# PSU-Unit.net
KiCad netlist of a schematic drawn in EAGLE
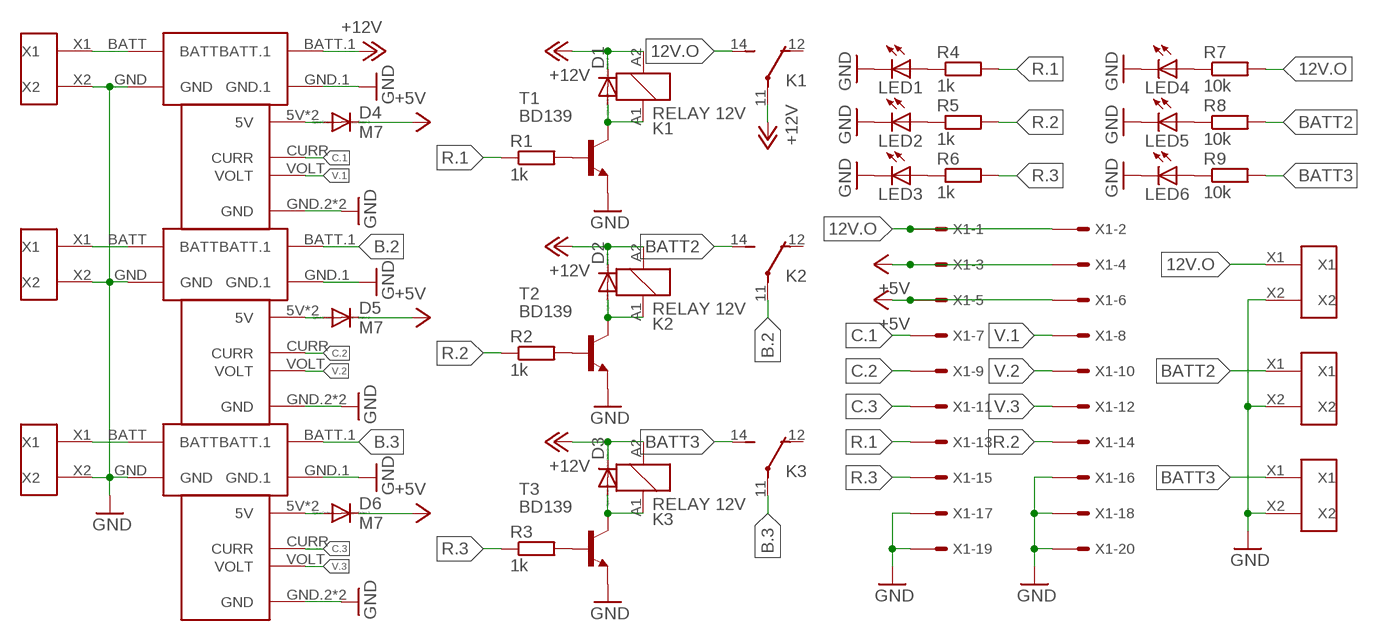
[diagram p0: schematic, sheet 1]

(export (version "E")
  (design (tool "Eeschema 10.0.6"))
  (components
    (comp (ref "D1")
      (value "DIODE-DO214AA")
      (footprint "eagle-import:DO214AA")
      (libsource (lib "eagle-import") (part "DIODE-DO214AA"))
    )
    (comp (ref "D2")
      (value "DIODE-DO214AA")
      (footprint "eagle-import:DO214AA")
      (libsource (lib "eagle-import") (part "DIODE-DO214AA"))
    )
    (comp (ref "D3")
      (value "DIODE-DO214AA")
      (footprint "eagle-import:DO214AA")
      (libsource (lib "eagle-import") (part "DIODE-DO214AA"))
    )
    (comp (ref "D4")
      (value "M7")
      (footprint "eagle-import:DO214AA")
      (libsource (lib "eagle-import") (part "DIODE-DO214AA"))
    )
    (comp (ref "D5")
      (value "M7")
      (footprint "eagle-import:DO214AA")
      (libsource (lib "eagle-import") (part "DIODE-DO214AA"))
    )
    (comp (ref "D6")
      (value "M7")
      (footprint "eagle-import:DO214AA")
      (libsource (lib "eagle-import") (part "DIODE-DO214AA"))
    )
    (comp (ref "K1")
      (value "RELAY 12V")
      (footprint "eagle-import:ZD1")
      (libsource (lib "eagle-import") (part "ZD?132006"))
    )
    (comp (ref "K2")
      (value "RELAY 12V")
      (footprint "eagle-import:ZD1")
      (libsource (lib "eagle-import") (part "ZD?132006"))
    )
    (comp (ref "K3")
      (value "RELAY 12V")
      (footprint "eagle-import:ZD1")
      (libsource (lib "eagle-import") (part "ZD?132006"))
    )
    (comp (ref "LED1")
      (value "LEDCHIPLED_1206")
      (footprint "eagle-import:CHIPLED_1206")
      (libsource (lib "eagle-import") (part "LEDCHIPLED_1206"))
    )
    (comp (ref "LED2")
      (value "LEDCHIPLED_1206")
      (footprint "eagle-import:CHIPLED_1206")
      (libsource (lib "eagle-import") (part "LEDCHIPLED_1206"))
    )
    (comp (ref "LED3")
      (value "LEDCHIPLED_1206")
      (footprint "eagle-import:CHIPLED_1206")
      (libsource (lib "eagle-import") (part "LEDCHIPLED_1206"))
    )
    (comp (ref "LED4")
      (value "LEDCHIPLED_1206")
      (footprint "eagle-import:CHIPLED_1206")
      (libsource (lib "eagle-import") (part "LEDCHIPLED_1206"))
    )
    (comp (ref "LED5")
      (value "LEDCHIPLED_1206")
      (footprint "eagle-import:CHIPLED_1206")
      (libsource (lib "eagle-import") (part "LEDCHIPLED_1206"))
    )
    (comp (ref "LED6")
      (value "LEDCHIPLED_1206")
      (footprint "eagle-import:CHIPLED_1206")
      (libsource (lib "eagle-import") (part "LEDCHIPLED_1206"))
    )
    (comp (ref "R1")
      (value "1k")
      (footprint "eagle-import:R0805")
      (libsource (lib "eagle-import") (part "R-EU_R0805"))
    )
    (comp (ref "R2")
      (value "1k")
      (footprint "eagle-import:R0805")
      (libsource (lib "eagle-import") (part "R-EU_R0805"))
    )
    (comp (ref "R3")
      (value "1k")
      (footprint "eagle-import:R0805")
      (libsource (lib "eagle-import") (part "R-EU_R0805"))
    )
    (comp (ref "R4")
      (value "1k")
      (footprint "eagle-import:R0805")
      (libsource (lib "eagle-import") (part "R-EU_R0805"))
    )
    (comp (ref "R5")
      (value "1k")
      (footprint "eagle-import:R0805")
      (libsource (lib "eagle-import") (part "R-EU_R0805"))
    )
    (comp (ref "R6")
      (value "1k")
      (footprint "eagle-import:R0805")
      (libsource (lib "eagle-import") (part "R-EU_R0805"))
    )
    (comp (ref "R7")
      (value "10k")
      (footprint "eagle-import:R0805")
      (libsource (lib "eagle-import") (part "R-EU_R0805"))
    )
    (comp (ref "R8")
      (value "10k")
      (footprint "eagle-import:R0805")
      (libsource (lib "eagle-import") (part "R-EU_R0805"))
    )
    (comp (ref "R9")
      (value "10k")
      (footprint "eagle-import:R0805")
      (libsource (lib "eagle-import") (part "R-EU_R0805"))
    )
    (comp (ref "T1")
      (value "BD139")
      (footprint "eagle-import:TO126V")
      (libsource (lib "eagle-import") (part "-NPN-TO126V"))
    )
    (comp (ref "T2")
      (value "BD139")
      (footprint "eagle-import:TO126V")
      (libsource (lib "eagle-import") (part "-NPN-TO126V"))
    )
    (comp (ref "T3")
      (value "BD139")
      (footprint "eagle-import:TO126V")
      (libsource (lib "eagle-import") (part "-NPN-TO126V"))
    )
    (comp (ref "U$1")
      (value "APM-POWER-MODULE")
      (footprint "eagle-import:APM-POWER-MODULE")
      (libsource (lib "eagle-import") (part "APM-POWER-MODULE"))
    )
    (comp (ref "U$2")
      (value "APM-MEASURAND")
      (footprint "eagle-import:APM-MEASURAND")
      (libsource (lib "eagle-import") (part "APM-MEASURAND"))
    )
    (comp (ref "U$3")
      (value "APM-POWER-MODULE")
      (footprint "eagle-import:APM-POWER-MODULE")
      (libsource (lib "eagle-import") (part "APM-POWER-MODULE"))
    )
    (comp (ref "U$4")
      (value "APM-MEASURAND")
      (footprint "eagle-import:APM-MEASURAND")
      (libsource (lib "eagle-import") (part "APM-MEASURAND"))
    )
    (comp (ref "U$5")
      (value "APM-POWER-MODULE")
      (footprint "eagle-import:APM-POWER-MODULE")
      (libsource (lib "eagle-import") (part "APM-POWER-MODULE"))
    )
    (comp (ref "U$6")
      (value "APM-MEASURAND")
      (footprint "eagle-import:APM-MEASURAND")
      (libsource (lib "eagle-import") (part "APM-MEASURAND"))
    )
    (comp (ref "U$7")
      (value "T-BLOCK-9.5MM")
      (footprint "eagle-import:T-BLOCK-9.5MM")
      (libsource (lib "eagle-import") (part "T-BLOCK-9.5MM"))
    )
    (comp (ref "U$8")
      (value "T-BLOCK-9.5MM")
      (footprint "eagle-import:T-BLOCK-9.5MM")
      (libsource (lib "eagle-import") (part "T-BLOCK-9.5MM"))
    )
    (comp (ref "U$9")
      (value "T-BLOCK-9.5MM")
      (footprint "eagle-import:T-BLOCK-9.5MM")
      (libsource (lib "eagle-import") (part "T-BLOCK-9.5MM"))
    )
    (comp (ref "U$10")
      (value "T-BLOCK-9.5MM")
      (footprint "eagle-import:T-BLOCK-9.5MM")
      (libsource (lib "eagle-import") (part "T-BLOCK-9.5MM"))
    )
    (comp (ref "U$11")
      (value "T-BLOCK-9.5MM")
      (footprint "eagle-import:T-BLOCK-9.5MM")
      (libsource (lib "eagle-import") (part "T-BLOCK-9.5MM"))
    )
    (comp (ref "U$12")
      (value "T-BLOCK-9.5MM")
      (footprint "eagle-import:T-BLOCK-9.5MM")
      (libsource (lib "eagle-import") (part "T-BLOCK-9.5MM"))
    )
    (comp (ref "X1")
      (value "057-020-1")
      (footprint "eagle-import:057-020-1")
      (libsource (lib "eagle-import") (part "057-020-1"))
    )
  )
  (nets
    (net (code "1") (name "+5V") (class "Default")
      (node (ref "D4") (pin "C") (pinfunction "C_C") (pintype "passive"))
      (node (ref "D5") (pin "C") (pinfunction "C_C") (pintype "passive"))
      (node (ref "D6") (pin "C") (pinfunction "C_C") (pintype "passive"))
      (node (ref "X1") (pin "3") (pinfunction "S_3") (pintype "passive"))
      (node (ref "X1") (pin "4") (pinfunction "S_4") (pintype "passive"))
      (node (ref "X1") (pin "5") (pinfunction "S_5") (pintype "passive"))
      (node (ref "X1") (pin "6") (pinfunction "S_6") (pintype "passive"))
    )
    (net (code "2") (name "+12V") (class "Default")
      (node (ref "D1") (pin "C") (pinfunction "C_C") (pintype "passive"))
      (node (ref "D2") (pin "C") (pinfunction "C_C") (pintype "passive"))
      (node (ref "D3") (pin "C") (pinfunction "C_C") (pintype "passive"))
      (node (ref "K1") (pin "11") (pinfunction "P_11") (pintype "passive"))
      (node (ref "K1") (pin "A2") (pinfunction "2_A2") (pintype "passive"))
      (node (ref "K2") (pin "A2") (pinfunction "2_A2") (pintype "passive"))
      (node (ref "K3") (pin "A2") (pinfunction "2_A2") (pintype "passive"))
      (node (ref "U$1") (pin "BATT.1") (pinfunction "BATT.1_BATT.1") (pintype "bidirectional"))
    )
    (net (code "3") (name "12V.O") (class "Default")
      (node (ref "K1") (pin "14") (pinfunction "S_14") (pintype "passive"))
      (node (ref "R7") (pin "2") (pinfunction "2_2") (pintype "passive"))
      (node (ref "U$10") (pin "X1") (pinfunction "X1_X1") (pintype "bidirectional"))
      (node (ref "X1") (pin "1") (pinfunction "S_1") (pintype "passive"))
      (node (ref "X1") (pin "2") (pinfunction "S_2") (pintype "passive"))
    )
    (net (code "4") (name "B.2") (class "Default")
      (node (ref "K2") (pin "11") (pinfunction "P_11") (pintype "passive"))
      (node (ref "U$3") (pin "BATT.1") (pinfunction "BATT.1_BATT.1") (pintype "bidirectional"))
    )
    (net (code "5") (name "B.3") (class "Default")
      (node (ref "K3") (pin "11") (pinfunction "P_11") (pintype "passive"))
      (node (ref "U$5") (pin "BATT.1") (pinfunction "BATT.1_BATT.1") (pintype "bidirectional"))
    )
    (net (code "6") (name "BATT2") (class "Default")
      (node (ref "K2") (pin "14") (pinfunction "S_14") (pintype "passive"))
      (node (ref "R8") (pin "2") (pinfunction "2_2") (pintype "passive"))
      (node (ref "U$11") (pin "X1") (pinfunction "X1_X1") (pintype "bidirectional"))
    )
    (net (code "7") (name "BATT3") (class "Default")
      (node (ref "K3") (pin "14") (pinfunction "S_14") (pintype "passive"))
      (node (ref "R9") (pin "2") (pinfunction "2_2") (pintype "passive"))
      (node (ref "U$12") (pin "X1") (pinfunction "X1_X1") (pintype "bidirectional"))
    )
    (net (code "8") (name "C.1") (class "Default")
      (node (ref "U$2") (pin "CURR") (pinfunction "CURR_CURR") (pintype "bidirectional"))
      (node (ref "X1") (pin "7") (pinfunction "S_7") (pintype "passive"))
    )
    (net (code "9") (name "C.2") (class "Default")
      (node (ref "U$4") (pin "CURR") (pinfunction "CURR_CURR") (pintype "bidirectional"))
      (node (ref "X1") (pin "9") (pinfunction "S_9") (pintype "passive"))
    )
    (net (code "10") (name "C.3") (class "Default")
      (node (ref "U$6") (pin "CURR") (pinfunction "CURR_CURR") (pintype "bidirectional"))
      (node (ref "X1") (pin "11") (pinfunction "S_11") (pintype "passive"))
    )
    (net (code "11") (name "GND") (class "Default")
      (node (ref "LED1") (pin "C") (pinfunction "C_C") (pintype "passive"))
      (node (ref "LED2") (pin "C") (pinfunction "C_C") (pintype "passive"))
      (node (ref "LED3") (pin "C") (pinfunction "C_C") (pintype "passive"))
      (node (ref "LED4") (pin "C") (pinfunction "C_C") (pintype "passive"))
      (node (ref "LED5") (pin "C") (pinfunction "C_C") (pintype "passive"))
      (node (ref "LED6") (pin "C") (pinfunction "C_C") (pintype "passive"))
      (node (ref "T1") (pin "1") (pinfunction "E_1") (pintype "passive"))
      (node (ref "T2") (pin "1") (pinfunction "E_1") (pintype "passive"))
      (node (ref "T3") (pin "1") (pinfunction "E_1") (pintype "passive"))
      (node (ref "U$1") (pin "GND") (pinfunction "GND_GND") (pintype "bidirectional"))
      (node (ref "U$1") (pin "GND.1") (pinfunction "GND.1_GND.1") (pintype "bidirectional"))
      (node (ref "U$10") (pin "X2") (pinfunction "X2_X2") (pintype "bidirectional"))
      (node (ref "U$11") (pin "X2") (pinfunction "X2_X2") (pintype "bidirectional"))
      (node (ref "U$12") (pin "X2") (pinfunction "X2_X2") (pintype "bidirectional"))
      (node (ref "U$2") (pin "GND.2") (pinfunction "GND_GND.2") (pintype "bidirectional"))
      (node (ref "U$2") (pin "GND.3") (pinfunction "GND_GND.3") (pintype "bidirectional"))
      (node (ref "U$3") (pin "GND") (pinfunction "GND_GND") (pintype "bidirectional"))
      (node (ref "U$3") (pin "GND.1") (pinfunction "GND.1_GND.1") (pintype "bidirectional"))
      (node (ref "U$4") (pin "GND.2") (pinfunction "GND_GND.2") (pintype "bidirectional"))
      (node (ref "U$4") (pin "GND.3") (pinfunction "GND_GND.3") (pintype "bidirectional"))
      (node (ref "U$5") (pin "GND") (pinfunction "GND_GND") (pintype "bidirectional"))
      (node (ref "U$5") (pin "GND.1") (pinfunction "GND.1_GND.1") (pintype "bidirectional"))
      (node (ref "U$6") (pin "GND.2") (pinfunction "GND_GND.2") (pintype "bidirectional"))
      (node (ref "U$6") (pin "GND.3") (pinfunction "GND_GND.3") (pintype "bidirectional"))
      (node (ref "U$7") (pin "X2") (pinfunction "X2_X2") (pintype "bidirectional"))
      (node (ref "U$8") (pin "X2") (pinfunction "X2_X2") (pintype "bidirectional"))
      (node (ref "U$9") (pin "X2") (pinfunction "X2_X2") (pintype "bidirectional"))
      (node (ref "X1") (pin "16") (pinfunction "S_16") (pintype "passive"))
      (node (ref "X1") (pin "17") (pinfunction "S_17") (pintype "passive"))
      (node (ref "X1") (pin "18") (pinfunction "S_18") (pintype "passive"))
      (node (ref "X1") (pin "19") (pinfunction "S_19") (pintype "passive"))
      (node (ref "X1") (pin "20") (pinfunction "S_20") (pintype "passive"))
    )
    (net (code "12") (name "Net-(D4-PadA)") (class "Default")
      (node (ref "D4") (pin "A") (pinfunction "A_A") (pintype "passive"))
      (node (ref "U$2") (pin "5V") (pinfunction "5V_5V") (pintype "bidirectional"))
      (node (ref "U$2") (pin "5V.1") (pinfunction "5V_5V.1") (pintype "bidirectional"))
    )
    (net (code "13") (name "Net-(D5-PadA)") (class "Default")
      (node (ref "D5") (pin "A") (pinfunction "A_A") (pintype "passive"))
      (node (ref "U$4") (pin "5V") (pinfunction "5V_5V") (pintype "bidirectional"))
      (node (ref "U$4") (pin "5V.1") (pinfunction "5V_5V.1") (pintype "bidirectional"))
    )
    (net (code "14") (name "Net-(D6-PadA)") (class "Default")
      (node (ref "D6") (pin "A") (pinfunction "A_A") (pintype "passive"))
      (node (ref "U$6") (pin "5V") (pinfunction "5V_5V") (pintype "bidirectional"))
      (node (ref "U$6") (pin "5V.1") (pinfunction "5V_5V.1") (pintype "bidirectional"))
    )
    (net (code "15") (name "Net-(K1A-1)") (class "Default")
      (node (ref "D1") (pin "A") (pinfunction "A_A") (pintype "passive"))
      (node (ref "K1") (pin "A1") (pinfunction "1_A1") (pintype "passive"))
      (node (ref "T1") (pin "2") (pinfunction "C_2") (pintype "passive"))
    )
    (net (code "16") (name "Net-(K2A-1)") (class "Default")
      (node (ref "D2") (pin "A") (pinfunction "A_A") (pintype "passive"))
      (node (ref "K2") (pin "A1") (pinfunction "1_A1") (pintype "passive"))
      (node (ref "T2") (pin "2") (pinfunction "C_2") (pintype "passive"))
    )
    (net (code "17") (name "Net-(K3A-1)") (class "Default")
      (node (ref "D3") (pin "A") (pinfunction "A_A") (pintype "passive"))
      (node (ref "K3") (pin "A1") (pinfunction "1_A1") (pintype "passive"))
      (node (ref "T3") (pin "2") (pinfunction "C_2") (pintype "passive"))
    )
    (net (code "18") (name "Net-(LED1-PadA)") (class "Default")
      (node (ref "LED1") (pin "A") (pinfunction "A_A") (pintype "passive"))
      (node (ref "R4") (pin "1") (pinfunction "1_1") (pintype "passive"))
    )
    (net (code "19") (name "Net-(LED2-PadA)") (class "Default")
      (node (ref "LED2") (pin "A") (pinfunction "A_A") (pintype "passive"))
      (node (ref "R5") (pin "1") (pinfunction "1_1") (pintype "passive"))
    )
    (net (code "20") (name "Net-(LED3-PadA)") (class "Default")
      (node (ref "LED3") (pin "A") (pinfunction "A_A") (pintype "passive"))
      (node (ref "R6") (pin "1") (pinfunction "1_1") (pintype "passive"))
    )
    (net (code "21") (name "Net-(LED4-PadA)") (class "Default")
      (node (ref "LED4") (pin "A") (pinfunction "A_A") (pintype "passive"))
      (node (ref "R7") (pin "1") (pinfunction "1_1") (pintype "passive"))
    )
    (net (code "22") (name "Net-(LED5-PadA)") (class "Default")
      (node (ref "LED5") (pin "A") (pinfunction "A_A") (pintype "passive"))
      (node (ref "R8") (pin "1") (pinfunction "1_1") (pintype "passive"))
    )
    (net (code "23") (name "Net-(LED6-PadA)") (class "Default")
      (node (ref "LED6") (pin "A") (pinfunction "A_A") (pintype "passive"))
      (node (ref "R9") (pin "1") (pinfunction "1_1") (pintype "passive"))
    )
    (net (code "24") (name "Net-(T1-B)") (class "Default")
      (node (ref "R1") (pin "2") (pinfunction "2_2") (pintype "passive"))
      (node (ref "T1") (pin "3") (pinfunction "B_3") (pintype "passive"))
    )
    (net (code "25") (name "Net-(T2-B)") (class "Default")
      (node (ref "R2") (pin "2") (pinfunction "2_2") (pintype "passive"))
      (node (ref "T2") (pin "3") (pinfunction "B_3") (pintype "passive"))
    )
    (net (code "26") (name "Net-(T3-B)") (class "Default")
      (node (ref "R3") (pin "2") (pinfunction "2_2") (pintype "passive"))
      (node (ref "T3") (pin "3") (pinfunction "B_3") (pintype "passive"))
    )
    (net (code "27") (name "Net-(U$1-PadBATT)") (class "Default")
      (node (ref "U$1") (pin "BATT") (pinfunction "BATT_BATT") (pintype "bidirectional"))
      (node (ref "U$7") (pin "X1") (pinfunction "X1_X1") (pintype "bidirectional"))
    )
    (net (code "28") (name "Net-(U$3-PadBATT)") (class "Default")
      (node (ref "U$3") (pin "BATT") (pinfunction "BATT_BATT") (pintype "bidirectional"))
      (node (ref "U$8") (pin "X1") (pinfunction "X1_X1") (pintype "bidirectional"))
    )
    (net (code "29") (name "Net-(U$5-PadBATT)") (class "Default")
      (node (ref "U$5") (pin "BATT") (pinfunction "BATT_BATT") (pintype "bidirectional"))
      (node (ref "U$9") (pin "X1") (pinfunction "X1_X1") (pintype "bidirectional"))
    )
    (net (code "30") (name "R.1") (class "Default")
      (node (ref "R1") (pin "1") (pinfunction "1_1") (pintype "passive"))
      (node (ref "R4") (pin "2") (pinfunction "2_2") (pintype "passive"))
      (node (ref "X1") (pin "13") (pinfunction "S_13") (pintype "passive"))
    )
    (net (code "31") (name "R.2") (class "Default")
      (node (ref "R2") (pin "1") (pinfunction "1_1") (pintype "passive"))
      (node (ref "R5") (pin "2") (pinfunction "2_2") (pintype "passive"))
      (node (ref "X1") (pin "14") (pinfunction "S_14") (pintype "passive"))
    )
    (net (code "32") (name "R.3") (class "Default")
      (node (ref "R3") (pin "1") (pinfunction "1_1") (pintype "passive"))
      (node (ref "R6") (pin "2") (pinfunction "2_2") (pintype "passive"))
      (node (ref "X1") (pin "15") (pinfunction "S_15") (pintype "passive"))
    )
    (net (code "33") (name "V.1") (class "Default")
      (node (ref "U$2") (pin "VOLT") (pinfunction "VOLT_VOLT") (pintype "bidirectional"))
      (node (ref "X1") (pin "8") (pinfunction "S_8") (pintype "passive"))
    )
    (net (code "34") (name "V.2") (class "Default")
      (node (ref "U$4") (pin "VOLT") (pinfunction "VOLT_VOLT") (pintype "bidirectional"))
      (node (ref "X1") (pin "10") (pinfunction "S_10") (pintype "passive"))
    )
    (net (code "35") (name "V.3") (class "Default")
      (node (ref "U$6") (pin "VOLT") (pinfunction "VOLT_VOLT") (pintype "bidirectional"))
      (node (ref "X1") (pin "12") (pinfunction "S_12") (pintype "passive"))
    )
    (net (code "36") (name "unconnected-(K1B-O-Pad12)") (class "Default")
      (node (ref "K1") (pin "12") (pinfunction "O_12") (pintype "passive"))
    )
    (net (code "37") (name "unconnected-(K2B-O-Pad12)") (class "Default")
      (node (ref "K2") (pin "12") (pinfunction "O_12") (pintype "passive"))
    )
    (net (code "38") (name "unconnected-(K3B-O-Pad12)") (class "Default")
      (node (ref "K3") (pin "12") (pinfunction "O_12") (pintype "passive"))
    )
  )
)
